# 1_Power.net
KiCad netlist of a schematic drawn in Altium Designer
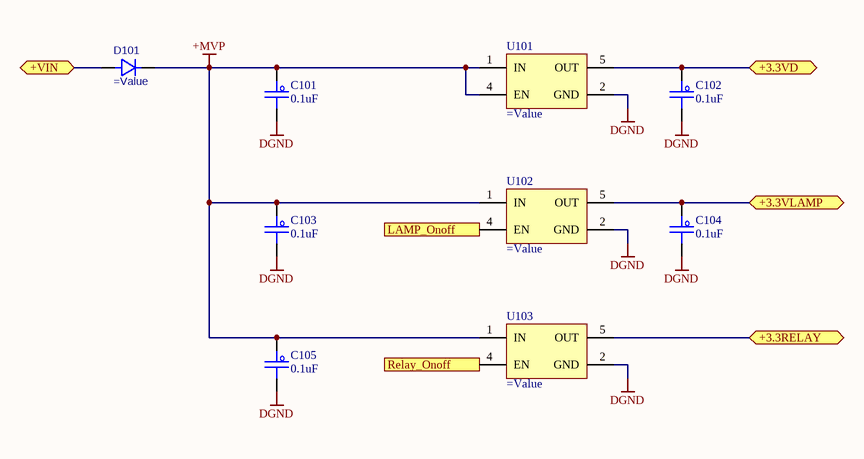
[diagram p0: 1_Power.SchDoc]

(export (version "E")
  (design (tool "Eeschema 10.0.6"))
  (components
    (comp (ref "C101")
      (value "0.1uF")
      (footprint "C_0603")
      (description "CAP CER 0.1UF 50V X7R 0603")
      (fields (field (name "MANUFACTURER") "KEMET") (field (name "PARTNUMBER") "C0603C104K5RACTU"))
      (libsource (lib "UUSymbol") (part "C_Capacitor"))
    )
    (comp (ref "C102")
      (value "0.1uF")
      (footprint "C_0603")
      (description "CAP CER 0.1UF 50V X7R 0603")
      (fields (field (name "MANUFACTURER") "KEMET") (field (name "PARTNUMBER") "C0603C104K5RACTU"))
      (libsource (lib "UUSymbol") (part "C_Capacitor"))
    )
    (comp (ref "C103")
      (value "0.1uF")
      (footprint "C_0603")
      (description "CAP CER 0.1UF 50V X7R 0603")
      (fields (field (name "MANUFACTURER") "KEMET") (field (name "PARTNUMBER") "C0603C104K5RACTU"))
      (libsource (lib "UUSymbol") (part "C_Capacitor"))
    )
    (comp (ref "C104")
      (value "0.1uF")
      (footprint "C_0603")
      (description "CAP CER 0.1UF 50V X7R 0603")
      (fields (field (name "MANUFACTURER") "KEMET") (field (name "PARTNUMBER") "C0603C104K5RACTU"))
      (libsource (lib "UUSymbol") (part "C_Capacitor"))
    )
    (comp (ref "C105")
      (value "0.1uF")
      (footprint "C_0603")
      (description "CAP CER 0.1UF 50V X7R 0603")
      (fields (field (name "MANUFACTURER") "KEMET") (field (name "PARTNUMBER") "C0603C104K5RACTU"))
      (libsource (lib "UUSymbol") (part "C_Capacitor"))
    )
    (comp (ref "D101")
      (value "~")
      (footprint "SOD323")
      (description "DIODE SCHOTTKY 40V 2A 0603")
      (fields (field (name "MANUFACTURER") "Slkor(SLKORMICRO Elec.)") (field (name "PARTNUMBER") "SD103AWS"))
      (libsource (lib "UUSymbol") (part "D_PW_SD103AWS"))
    )
    (comp (ref "U101")
      (value "~")
      (footprint "SOT95P280X145-5N")
      (description "200mA 360mV@(10mA) Fixed 3.3V~3.3V Positive 1 36V SOT-23-5 Linear Voltage Regulators (LDO) ROHS")
      (fields (field (name "PARTNUMBER") "RT9069-33GB") (field (name "MANUFACTURER") "Richtek Tech"))
      (libsource (lib "UUSymbol") (part "IC_LDO_RT9069-33GB"))
    )
    (comp (ref "U102")
      (value "~")
      (footprint "SOT95P280X145-5N")
      (description "200mA 360mV@(10mA) Fixed 3.3V~3.3V Positive 1 36V SOT-23-5 Linear Voltage Regulators (LDO) ROHS")
      (fields (field (name "PARTNUMBER") "RT9069-33GB") (field (name "MANUFACTURER") "Richtek Tech"))
      (libsource (lib "UUSymbol") (part "IC_LDO_RT9069-33GB"))
    )
    (comp (ref "U103")
      (value "~")
      (footprint "SOT95P280X145-5N")
      (description "200mA 360mV@(10mA) Fixed 3.3V~3.3V Positive 1 36V SOT-23-5 Linear Voltage Regulators (LDO) ROHS")
      (fields (field (name "PARTNUMBER") "RT9069-33GB") (field (name "MANUFACTURER") "Richtek Tech"))
      (libsource (lib "UUSymbol") (part "IC_LDO_RT9069-33GB"))
    )
  )
  (nets
    (net (code "1") (name "+MVP") (class "Default")
      (node (ref "C101") (pin "1") (pinfunction "1_1") (pintype "passive"))
      (node (ref "C103") (pin "1") (pinfunction "1_1") (pintype "passive"))
      (node (ref "C105") (pin "1") (pinfunction "1_1") (pintype "passive"))
      (node (ref "D101") (pin "1") (pinfunction "1_1") (pintype "passive"))
      (node (ref "U101") (pin "1") (pinfunction "IN_1") (pintype "passive"))
      (node (ref "U101") (pin "4") (pinfunction "EN_4") (pintype "passive"))
      (node (ref "U102") (pin "1") (pinfunction "IN_1") (pintype "passive"))
      (node (ref "U103") (pin "1") (pinfunction "IN_1") (pintype "passive"))
    )
    (net (code "2") (name "/+3.3RELAY") (class "Default")
      (node (ref "U103") (pin "5") (pinfunction "OUT_5") (pintype "passive"))
    )
    (net (code "3") (name "/+3.3VD") (class "Default")
      (node (ref "C102") (pin "1") (pinfunction "1_1") (pintype "passive"))
      (node (ref "U101") (pin "5") (pinfunction "OUT_5") (pintype "passive"))
    )
    (net (code "4") (name "/+3.3VLAMP") (class "Default")
      (node (ref "C104") (pin "1") (pinfunction "1_1") (pintype "passive"))
      (node (ref "U102") (pin "5") (pinfunction "OUT_5") (pintype "passive"))
    )
    (net (code "5") (name "/+VIN") (class "Default")
      (node (ref "D101") (pin "2") (pinfunction "2_2") (pintype "passive"))
    )
    (net (code "6") (name "/LAMP_Onoff") (class "Default")
      (node (ref "U102") (pin "4") (pinfunction "EN_4") (pintype "passive"))
    )
    (net (code "7") (name "/Relay_Onoff") (class "Default")
      (node (ref "U103") (pin "4") (pinfunction "EN_4") (pintype "passive"))
    )
    (net (code "8") (name "DGND") (class "Default")
      (node (ref "C101") (pin "2") (pinfunction "2_2") (pintype "passive"))
      (node (ref "C102") (pin "2") (pinfunction "2_2") (pintype "passive"))
      (node (ref "C103") (pin "2") (pinfunction "2_2") (pintype "passive"))
      (node (ref "C104") (pin "2") (pinfunction "2_2") (pintype "passive"))
      (node (ref "C105") (pin "2") (pinfunction "2_2") (pintype "passive"))
      (node (ref "U101") (pin "2") (pinfunction "GND_2") (pintype "passive"))
      (node (ref "U102") (pin "2") (pinfunction "GND_2") (pintype "passive"))
      (node (ref "U103") (pin "2") (pinfunction "GND_2") (pintype "passive"))
    )
  )
)
